# power-v5v5n.net
KiCad netlist of a schematic drawn in Altium Designer
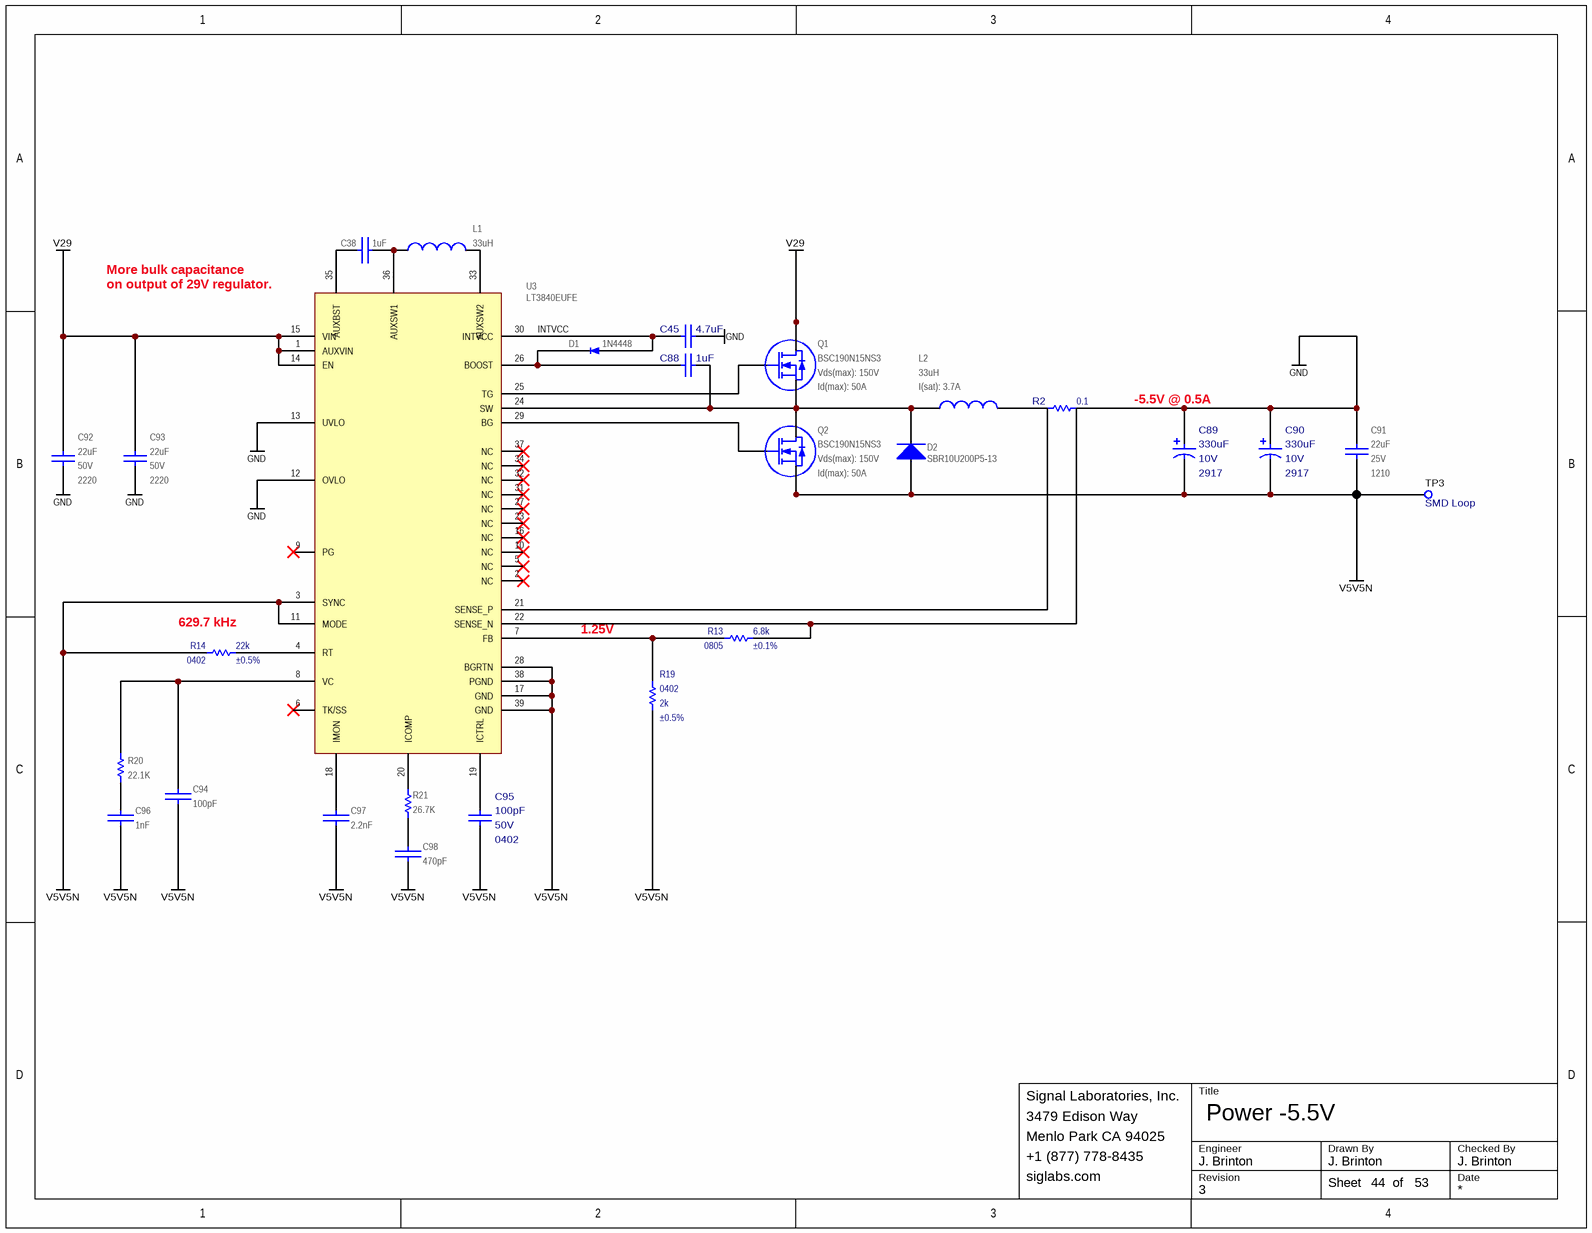
[diagram p0: power-v5v5n.SchDoc]

(export (version "E")
  (design (tool "Eeschema 10.0.6"))
  (components
    (comp (ref "C38")
      (value "1uF")
      (footprint "CAPC100X50X55L25N")
      (description "Ceramic Capacitor 1uF ±10% 10V X5R 0402")
      (fields (field (name "MANUFACTURER") "Murata") (field (name "TOLERANCE") "±10%"))
      (libsource (lib "*") (part "CAP"))
    )
    (comp (ref "C45")
      (value "4.7uF")
      (footprint "CAPC160X80X90L20N")
      (description "Ceramic Capacitor 4.7uF ±10% 25V X5R 0603")
      (fields (field (name "MANUFACTURER") "Samsung") (field (name "TOLERANCE") "±10%"))
      (libsource (lib "capacitors") (part "CAP"))
    )
    (comp (ref "C88")
      (value "1uF")
      (footprint "CAPC100X50X55L25N")
      (description "Ceramic Capacitor 1uF ±10% 10V X5R 0402")
      (fields (field (name "MANUFACTURER") "Murata") (field (name "TOLERANCE") "±10%"))
      (libsource (lib "capacitors") (part "CAP"))
    )
    (comp (ref "C89")
      (value "330uF")
      (footprint "CAPPM730X435X310L135X240N")
      (description "Tantalum Capacitor 330uF ±10% 10V 2917")
      (fields
        (field (name "MANUFACTURER") "AVX")
        (field (name "TOLERANCE") "±10%")
        (field (name "PACKAGE") "2917")
        (field (name "VOLTAGE") "10V")
      )
      (libsource (lib "avx") (part "CAP_POL"))
    )
    (comp (ref "C90")
      (value "330uF")
      (footprint "CAPPM730X435X310L135X240N")
      (description "Tantalum Capacitor 330uF ±10% 10V 2917")
      (fields
        (field (name "MANUFACTURER") "AVX")
        (field (name "TOLERANCE") "±10%")
        (field (name "PACKAGE") "2917")
        (field (name "VOLTAGE") "10V")
      )
      (libsource (lib "avx") (part "CAP_POL"))
    )
    (comp (ref "C91")
      (value "22uF")
      (footprint "CAPC320X250X270L50N")
      (description "Ceramic Capacitor 22uF ±10% 25V X7R 1210")
      (fields
        (field (name "MANUFACTURER") "Murata")
        (field (name "TOLERANCE") "±10%")
        (field (name "VOLTAGE") "25V")
        (field (name "PACKAGE") "1210")
      )
      (libsource (lib "generic") (part "CAP"))
    )
    (comp (ref "C92")
      (value "22uF")
      (footprint "CAPC600X500X500L160N")
      (description "Ceramic Capacitor 22uF ±20% 50V X7S Stacked")
      (fields
        (field (name "MANUFACTURER") "TDK")
        (field (name "TOLERANCE") "±20%")
        (field (name "VOLTAGE") "50V")
        (field (name "PACKAGE") "2220")
      )
      (libsource (lib "generic") (part "CAP"))
    )
    (comp (ref "C93")
      (value "22uF")
      (footprint "CAPC600X500X500L160N")
      (description "Ceramic Capacitor 22uF ±20% 50V X7S Stacked")
      (fields
        (field (name "MANUFACTURER") "TDK")
        (field (name "TOLERANCE") "±20%")
        (field (name "VOLTAGE") "50V")
        (field (name "PACKAGE") "2220")
      )
      (libsource (lib "generic") (part "CAP"))
    )
    (comp (ref "C94")
      (value "100pF")
      (footprint "CAPC100X50X55L25N")
      (description "Ceramic Capacitor 100pF ±5% 50V NP0 0402")
      (fields (field (name "MANUFACTURER") "Murata") (field (name "VOLTAGE") "50V"))
      (libsource (lib "*") (part "CAP"))
    )
    (comp (ref "C95")
      (value "100pF")
      (footprint "generic:CAPC100X50X55L25N")
      (description "Ceramic Capacitor 100pF ±10% 50V C0G 0402")
      (fields
        (field (name "MANUFACTURER") "Vishay")
        (field (name "TOLERANCE") "±10%")
        (field (name "PACKAGE") "0402")
        (field (name "VOLTAGE") "50V")
      )
      (libsource (lib "capacitors") (part "CAP"))
    )
    (comp (ref "C96")
      (value "1nF")
      (footprint "CAPC100X50X55L25N")
      (description "Ceramic Capacitor 1nF ±5% 50V NP0 0402")
      (fields (field (name "MANUFACTURER") "Murata") (field (name "VOLTAGE") "50V"))
      (libsource (lib "*") (part "CAP"))
    )
    (comp (ref "C97")
      (value "2.2nF")
      (footprint "CAPC100X50X55L25N")
      (description "Ceramic Capacitor 2.2nF ±5% 25V NP0 0402")
      (fields (field (name "MANUFACTURER") "Kemet") (field (name "TOLERANCE") "±5%"))
      (libsource (lib "*") (part "CAP"))
    )
    (comp (ref "C98")
      (value "470pF")
      (footprint "CAPC100X50X55L25N")
      (description "Ceramic Capacitor 470pF ±5% 50V X7R 0402")
      (fields (field (name "MANUFACTURER") "Murata") (field (name "VOLTAGE") "50V"))
      (libsource (lib "*") (part "CAP"))
    )
    (comp (ref "D1")
      (value "1N4448HWS-7-F")
      (footprint "diodes_inc:SOD323")
      (description "Schottky Diode 80V 250mA SOD323")
      (fields (field (name "MANUFACTURER") "Diodes Inc") (field (name "ALTERNATIVE P/N") "1N4448"))
      (libsource (lib "diodes_inc") (part "1N4448HWS-7-F"))
    )
    (comp (ref "D2")
      (value "SBR10U200P5-13")
      (footprint "DIODES_POWERDI5")
      (description "Schottky Diode 200V 10A SMD")
      (fields (field (name "MANUFACTURER") "Diodes Inc"))
      (libsource (lib "diodes_inc") (part "PDS5100H"))
    )
    (comp (ref "L1")
      (value "33uH")
      (footprint "coilcraft:ME3220")
      (description "Inductor 33uH ±10% 500mA SMD")
      (fields (field (name "MANUFACTURER") "Coilcraft") (field (name "TOLERANCE") "±10%"))
      (libsource (lib "CamBoard_Pico_70.19K") (part "COIL"))
    )
    (comp (ref "L2")
      (value "33uH")
      (footprint "coilcraft:XAL6060")
      (description "Inductor 33uH,3.7A(sat), SMD")
      (fields
        (field (name "MANUFACTURER") "Coilcraft")
        (field (name "I(SAT)") "3.7A")
        (field (name "Comment") "XAL6060-333ME")
      )
      (libsource (lib "CamBoard_Pico_70.19K") (part "COIL"))
    )
    (comp (ref "Q1")
      (value "BSC190N15NS3")
      (footprint "TDSON-8")
      (description "MOSFET N-Channel Enhancement Mode")
      (fields
        (field (name "MANUFACTURER") "Infineon")
        (field (name "VDS(MAX)") "150V")
        (field (name "ID(MAX)") "50A")
      )
      (libsource (lib "infinion") (part "BSC190N15NS3"))
    )
    (comp (ref "Q2")
      (value "BSC190N15NS3")
      (footprint "TDSON-8")
      (description "MOSFET N-Channel Enhancement Mode")
      (fields
        (field (name "MANUFACTURER") "Infineon")
        (field (name "VDS(MAX)") "150V")
        (field (name "ID(MAX)") "50A")
      )
      (libsource (lib "infinion") (part "BSC190N15NS3"))
    )
    (comp (ref "R2")
      (value "0.1")
      (footprint "susumu:KRL3216T4")
      (description "Current Sense Resistor 100 mOhms +/-1% SMD 4-Terminal")
      (fields (field (name "TOLERANCE") "±1%") (field (name "MANUFACTURER") "Susumu"))
      (libsource (lib "susumu") (part "KRL3216T4A-M-R009-F"))
    )
    (comp (ref "R13")
      (value "6.8k")
      (footprint "RESC2012X70N")
      (description "Thin Film Resistor 6.8k +/-0.1% SMD 0805")
      (fields
        (field (name "TOLERANCE") "±0.1%")
        (field (name "MANUFACTURER") "Susumu")
        (field (name "PACKAGE") "0805")
        (field (name "Comment") "RG2012P-682-B-T5")
      )
      (libsource (lib "generic") (part "RES"))
    )
    (comp (ref "R14")
      (value "22k")
      (footprint "RESC1005X40N")
      (description "Thin Film Resistor 22k +/-0.5% SMD 0402")
      (fields
        (field (name "TOLERANCE") "±0.5%")
        (field (name "MANUFACTURER") "Susumu")
        (field (name "PACKAGE") "0402")
        (field (name "Comment") "RR0510P-223-D")
      )
      (libsource (lib "generic") (part "RES"))
    )
    (comp (ref "R19")
      (value "2k")
      (footprint "RESC1005X40N")
      (description "Thin Film Resistor 2k +/-0.5% SMD 0402")
      (fields
        (field (name "TOLERANCE") "±0.5%")
        (field (name "MANUFACTURER") "Susumu")
        (field (name "PACKAGE") "0402")
        (field (name "Comment") "RR0510P-202-D")
      )
      (libsource (lib "generic") (part "RES"))
    )
    (comp (ref "R20")
      (value "22.1K")
      (footprint "generic:RESC1005X40N")
      (description "Thick Film Resistor 22.1k ±1% 0402")
      (fields (field (name "MANUFACTURER") "Panasonic") (field (name "TOLERANCE") "±1%"))
      (libsource (lib "Graviton") (part "RES 0402"))
    )
    (comp (ref "R21")
      (value "26.7K")
      (footprint "generic:RESC1005X40N")
      (description "Thick Film Resistor 26.7k ±1% 0402")
      (fields (field (name "MANUFACTURER") "Panasonic") (field (name "TOLERANCE") "±1%"))
      (libsource (lib "Graviton") (part "RES 0402"))
    )
    (comp (ref "TP3")
      (value "5015")
      (footprint "keystone:5015")
      (description "Test Point SMD")
      (fields (field (name "MANUFACTURER") "Keystone") (field (name "NOTES") "SMD Loop"))
      (libsource (lib "generic") (part "TEST_POINT_SMD_50"))
    )
    (comp (ref "U3")
      (value "LT3840EUFE")
      (footprint "linear:QFN39P40_600X400X80L40X20T465X265N")
      (description "Synchronous Regulator Controller")
      (fields (field (name "MANUFACTURER") "Linear Technology"))
      (libsource (lib "linear") (part "LT3840EUFE"))
    )
  )
  (nets
    (net (code "1") (name "/INTVCC") (class "Default")
      (node (ref "C45") (pin "1") (pinfunction "1_1") (pintype "passive"))
      (node (ref "D1") (pin "A") (pinfunction "A_A") (pintype "passive"))
      (node (ref "U3") (pin "30") (pinfunction "INTVCC_30") (pintype "passive"))
    )
    (net (code "2") (name "GND") (class "Default")
      (node (ref "C45") (pin "2") (pinfunction "2_2") (pintype "passive"))
      (node (ref "C89") (pin "1") (pinfunction "1_1") (pintype "passive"))
      (node (ref "C90") (pin "1") (pinfunction "1_1") (pintype "passive"))
      (node (ref "C91") (pin "2") (pinfunction "2_2") (pintype "passive"))
      (node (ref "C92") (pin "1") (pinfunction "1_1") (pintype "passive"))
      (node (ref "C93") (pin "1") (pinfunction "1_1") (pintype "passive"))
      (node (ref "R2") (pin "1") (pinfunction "1_1") (pintype "passive"))
      (node (ref "U3") (pin "12") (pinfunction "OVLO_12") (pintype "passive"))
      (node (ref "U3") (pin "13") (pinfunction "UVLO_13") (pintype "passive"))
    )
    (net (code "3") (name "Net-(C96-Pad1)") (class "Default")
      (node (ref "C96") (pin "1") (pinfunction "1_1") (pintype "passive"))
      (node (ref "R20") (pin "1") (pinfunction "1_1") (pintype "passive"))
    )
    (net (code "4") (name "Net-(C98-Pad2)") (class "Default")
      (node (ref "C98") (pin "2") (pinfunction "2_2") (pintype "passive"))
      (node (ref "R21") (pin "2") (pinfunction "2_2") (pintype "passive"))
    )
    (net (code "5") (name "Net-(L2-Pad2)") (class "Default")
      (node (ref "L2") (pin "2") (pinfunction "2_2") (pintype "passive"))
      (node (ref "R2") (pin "2") (pinfunction "2_2") (pintype "passive"))
    )
    (net (code "6") (name "Net-(Q1-G)") (class "Default")
      (node (ref "Q1") (pin "4") (pinfunction "G_4") (pintype "passive"))
      (node (ref "U3") (pin "25") (pinfunction "TG_25") (pintype "passive"))
    )
    (net (code "7") (name "Net-(Q2-G)") (class "Default")
      (node (ref "Q2") (pin "4") (pinfunction "G_4") (pintype "passive"))
      (node (ref "U3") (pin "29") (pinfunction "BG_29") (pintype "passive"))
    )
    (net (code "8") (name "Net-(U3-AUXBST)") (class "Default")
      (node (ref "C38") (pin "2") (pinfunction "2_2") (pintype "passive"))
      (node (ref "U3") (pin "35") (pinfunction "AUXBST_35") (pintype "passive"))
    )
    (net (code "9") (name "Net-(U3-AUXSW1)") (class "Default")
      (node (ref "C38") (pin "1") (pinfunction "1_1") (pintype "passive"))
      (node (ref "L1") (pin "1") (pinfunction "1_1") (pintype "passive"))
      (node (ref "U3") (pin "36") (pinfunction "AUXSW1_36") (pintype "passive"))
    )
    (net (code "10") (name "Net-(U3-AUXSW2)") (class "Default")
      (node (ref "L1") (pin "2") (pinfunction "2_2") (pintype "passive"))
      (node (ref "U3") (pin "33") (pinfunction "AUXSW2_33") (pintype "passive"))
    )
    (net (code "11") (name "Net-(U3-BOOST)") (class "Default")
      (node (ref "C88") (pin "1") (pinfunction "1_1") (pintype "passive"))
      (node (ref "D1") (pin "K") (pinfunction "K_K") (pintype "passive"))
      (node (ref "U3") (pin "26") (pinfunction "BOOST_26") (pintype "passive"))
    )
    (net (code "12") (name "Net-(U3-FB)") (class "Default")
      (node (ref "R13") (pin "2") (pinfunction "2_2") (pintype "passive"))
      (node (ref "R19") (pin "2") (pinfunction "2_2") (pintype "passive"))
      (node (ref "U3") (pin "7") (pinfunction "FB_7") (pintype "passive"))
    )
    (net (code "13") (name "Net-(U3-ICOMP)") (class "Default")
      (node (ref "R21") (pin "1") (pinfunction "1_1") (pintype "passive"))
      (node (ref "U3") (pin "20") (pinfunction "ICOMP_20") (pintype "passive"))
    )
    (net (code "14") (name "Net-(U3-ICTRL)") (class "Default")
      (node (ref "C95") (pin "1") (pinfunction "1_1") (pintype "passive"))
      (node (ref "U3") (pin "19") (pinfunction "ICTRL_19") (pintype "passive"))
    )
    (net (code "15") (name "Net-(U3-IMON)") (class "Default")
      (node (ref "C97") (pin "1") (pinfunction "1_1") (pintype "passive"))
      (node (ref "U3") (pin "18") (pinfunction "IMON_18") (pintype "passive"))
    )
    (net (code "16") (name "Net-(U3-RT)") (class "Default")
      (node (ref "R14") (pin "1") (pinfunction "1_1") (pintype "passive"))
      (node (ref "U3") (pin "4") (pinfunction "RT_4") (pintype "passive"))
    )
    (net (code "17") (name "Net-(U3-SENSE_N)") (class "Default")
      (node (ref "R13") (pin "1") (pinfunction "1_1") (pintype "passive"))
      (node (ref "R2") (pin "3") (pinfunction "3_3") (pintype "passive"))
      (node (ref "U3") (pin "22") (pinfunction "SENSE_N_22") (pintype "passive"))
    )
    (net (code "18") (name "Net-(U3-SENSE_P)") (class "Default")
      (node (ref "R2") (pin "4") (pinfunction "4_4") (pintype "passive"))
      (node (ref "U3") (pin "21") (pinfunction "SENSE_P_21") (pintype "passive"))
    )
    (net (code "19") (name "Net-(U3-SW)") (class "Default")
      (node (ref "C88") (pin "2") (pinfunction "2_2") (pintype "passive"))
      (node (ref "D2") (pin "K") (pinfunction "K_K") (pintype "passive"))
      (node (ref "L2") (pin "1") (pinfunction "1_1") (pintype "passive"))
      (node (ref "Q1") (pin "1") (pinfunction "S_1") (pintype "passive"))
      (node (ref "Q1") (pin "2") (pinfunction "S_2") (pintype "passive"))
      (node (ref "Q1") (pin "3") (pinfunction "S_3") (pintype "passive"))
      (node (ref "Q2") (pin "5") (pinfunction "D_5") (pintype "passive"))
      (node (ref "Q2") (pin "6") (pinfunction "D_6") (pintype "passive"))
      (node (ref "Q2") (pin "7") (pinfunction "D_7") (pintype "passive"))
      (node (ref "Q2") (pin "8") (pinfunction "D_8") (pintype "passive"))
      (node (ref "Q2") (pin "9") (pinfunction "D_9") (pintype "passive"))
      (node (ref "U3") (pin "24") (pinfunction "SW_24") (pintype "passive"))
    )
    (net (code "20") (name "Net-(U3-VC)") (class "Default")
      (node (ref "C94") (pin "2") (pinfunction "2_2") (pintype "passive"))
      (node (ref "R20") (pin "2") (pinfunction "2_2") (pintype "passive"))
      (node (ref "U3") (pin "8") (pinfunction "VC_8") (pintype "passive"))
    )
    (net (code "21") (name "V5V5N") (class "Default")
      (node (ref "C89") (pin "2") (pinfunction "2_2") (pintype "passive"))
      (node (ref "C90") (pin "2") (pinfunction "2_2") (pintype "passive"))
      (node (ref "C91") (pin "1") (pinfunction "1_1") (pintype "passive"))
      (node (ref "C94") (pin "1") (pinfunction "1_1") (pintype "passive"))
      (node (ref "C95") (pin "2") (pinfunction "2_2") (pintype "passive"))
      (node (ref "C96") (pin "2") (pinfunction "2_2") (pintype "passive"))
      (node (ref "C97") (pin "2") (pinfunction "2_2") (pintype "passive"))
      (node (ref "C98") (pin "1") (pinfunction "1_1") (pintype "passive"))
      (node (ref "D2") (pin "A") (pinfunction "A_A") (pintype "power_in"))
      (node (ref "Q2") (pin "1") (pinfunction "S_1") (pintype "passive"))
      (node (ref "Q2") (pin "2") (pinfunction "S_2") (pintype "passive"))
      (node (ref "Q2") (pin "3") (pinfunction "S_3") (pintype "passive"))
      (node (ref "R14") (pin "2") (pinfunction "2_2") (pintype "passive"))
      (node (ref "R19") (pin "1") (pinfunction "1_1") (pintype "passive"))
      (node (ref "TP3") (pin "1") (pinfunction "1_1") (pintype "passive"))
      (node (ref "U3") (pin "11") (pinfunction "MODE_11") (pintype "passive"))
      (node (ref "U3") (pin "17") (pinfunction "GND_17") (pintype "passive"))
      (node (ref "U3") (pin "28") (pinfunction "BGRTN_28") (pintype "passive"))
      (node (ref "U3") (pin "3") (pinfunction "SYNC_3") (pintype "passive"))
      (node (ref "U3") (pin "38") (pinfunction "PGND_38") (pintype "passive"))
      (node (ref "U3") (pin "39") (pinfunction "GND_39") (pintype "passive"))
    )
    (net (code "22") (name "V29") (class "Default")
      (node (ref "C92") (pin "2") (pinfunction "2_2") (pintype "passive"))
      (node (ref "C93") (pin "2") (pinfunction "2_2") (pintype "passive"))
      (node (ref "Q1") (pin "5") (pinfunction "D_5") (pintype "passive"))
      (node (ref "Q1") (pin "6") (pinfunction "D_6") (pintype "passive"))
      (node (ref "Q1") (pin "7") (pinfunction "D_7") (pintype "passive"))
      (node (ref "Q1") (pin "8") (pinfunction "D_8") (pintype "passive"))
      (node (ref "Q1") (pin "9") (pinfunction "D_9") (pintype "passive"))
      (node (ref "U3") (pin "1") (pinfunction "AUXVIN_1") (pintype "passive"))
      (node (ref "U3") (pin "14") (pinfunction "EN_14") (pintype "passive"))
      (node (ref "U3") (pin "15") (pinfunction "VIN_15") (pintype "passive"))
    )
    (net (code "23") (name "unconnected-(U3-NC-Pad2)") (class "Default")
      (node (ref "U3") (pin "2") (pinfunction "NC_2") (pintype "passive+no_connect"))
    )
    (net (code "24") (name "unconnected-(U3-NC-Pad5)") (class "Default")
      (node (ref "U3") (pin "5") (pinfunction "NC_5") (pintype "passive+no_connect"))
    )
    (net (code "25") (name "unconnected-(U3-NC-Pad10)") (class "Default")
      (node (ref "U3") (pin "10") (pinfunction "NC_10") (pintype "passive+no_connect"))
    )
    (net (code "26") (name "unconnected-(U3-NC-Pad16)") (class "Default")
      (node (ref "U3") (pin "16") (pinfunction "NC_16") (pintype "passive+no_connect"))
    )
    (net (code "27") (name "unconnected-(U3-NC-Pad23)") (class "Default")
      (node (ref "U3") (pin "23") (pinfunction "NC_23") (pintype "passive+no_connect"))
    )
    (net (code "28") (name "unconnected-(U3-NC-Pad27)") (class "Default")
      (node (ref "U3") (pin "27") (pinfunction "NC_27") (pintype "passive+no_connect"))
    )
    (net (code "29") (name "unconnected-(U3-NC-Pad31)") (class "Default")
      (node (ref "U3") (pin "31") (pinfunction "NC_31") (pintype "passive+no_connect"))
    )
    (net (code "30") (name "unconnected-(U3-NC-Pad32)") (class "Default")
      (node (ref "U3") (pin "32") (pinfunction "NC_32") (pintype "passive+no_connect"))
    )
    (net (code "31") (name "unconnected-(U3-NC-Pad34)") (class "Default")
      (node (ref "U3") (pin "34") (pinfunction "NC_34") (pintype "passive+no_connect"))
    )
    (net (code "32") (name "unconnected-(U3-NC-Pad37)") (class "Default")
      (node (ref "U3") (pin "37") (pinfunction "NC_37") (pintype "passive+no_connect"))
    )
    (net (code "33") (name "unconnected-(U3-PG-Pad9)") (class "Default")
      (node (ref "U3") (pin "9") (pinfunction "PG_9") (pintype "passive+no_connect"))
    )
    (net (code "34") (name "unconnected-(U3-TK{slash}SS-Pad6)") (class "Default")
      (node (ref "U3") (pin "6") (pinfunction "TK/SS_6") (pintype "passive+no_connect"))
    )
  )
)
